# Power_Input.net
KiCad netlist of a schematic drawn in Altium Designer
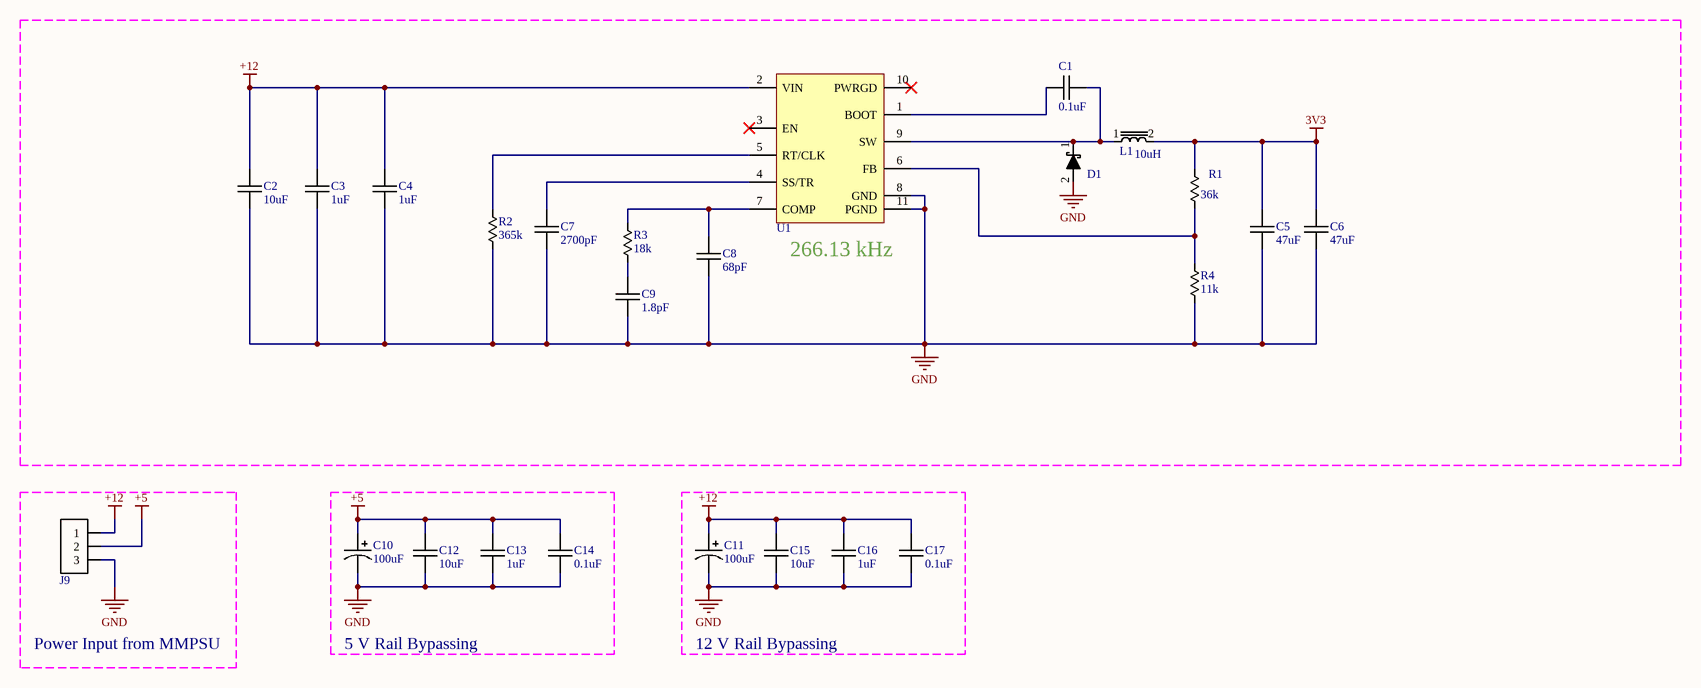
[diagram p0: Power_Input.SchDoc]

(export (version "E")
  (design (tool "Eeschema 10.0.6"))
  (components
    (comp (ref "C1")
      (value "0.1uF")
      (footprint "chip_0603")
      (description "CAP, 0.1uF, ±10%, 16V, X7R, 0603")
      (fields (field (name "PART NUMBER") "CAP-00542") (field (name "TOLERANCE") "±10%"))
      (libsource (lib "Capacitors$") (part "CAP-00542"))
    )
    (comp (ref "C2")
      (value "10uF")
      (footprint "chip_1206")
      (description "CAP, 10uF, ±10%, 25V, X7R, 1206")
      (fields (field (name "PART NUMBER") "CAP-00539") (field (name "TOLERANCE") "±10%"))
      (libsource (lib "Capacitors$") (part "CAP-00539"))
    )
    (comp (ref "C3")
      (value "1uF")
      (footprint "chip_0805")
      (description "CAP, 1uF, 10%, 25V, X7R, 0805")
      (fields (field (name "PART NUMBER") "CAP-00108") (field (name "TOLERANCE") "10%"))
      (libsource (lib "Capacitors$") (part "CAP-00108"))
    )
    (comp (ref "C4")
      (value "1uF")
      (footprint "chip_0805")
      (description "CAP, 1uF, 10%, 25V, X7R, 0805")
      (fields (field (name "PART NUMBER") "CAP-00108") (field (name "TOLERANCE") "10%"))
      (libsource (lib "Capacitors$") (part "CAP-00108"))
    )
    (comp (ref "C5")
      (value "47uF")
      (footprint "chip_1210")
      (description "CAP, 47uF, ±20%, 10V, X7R, 1210")
      (fields (field (name "PART NUMBER") "CAP-00593") (field (name "TOLERANCE") "±20%"))
      (libsource (lib "Capacitors$") (part "CAP-00593"))
    )
    (comp (ref "C6")
      (value "47uF")
      (footprint "chip_1210")
      (description "CAP, 47uF, ±20%, 10V, X7R, 1210")
      (fields (field (name "PART NUMBER") "CAP-00593") (field (name "TOLERANCE") "±20%"))
      (libsource (lib "Capacitors$") (part "CAP-00593"))
    )
    (comp (ref "C7")
      (value "2700pF")
      (footprint "chip_0603")
      (description "CAP, 2700pF, ±2%, 50V, C0G, 0603")
      (fields (field (name "PART NUMBER") "CAP-00434") (field (name "TOLERANCE") "±2%"))
      (libsource (lib "Capacitors$") (part "CAP-00434"))
    )
    (comp (ref "C8")
      (value "68pF")
      (footprint "chip_0603")
      (description "CAP, 68pF, ±2%, 50V, C0G, 0603")
      (fields (field (name "PART NUMBER") "CAP-00462") (field (name "TOLERANCE") "±2%"))
      (libsource (lib "Capacitors$") (part "CAP-00462"))
    )
    (comp (ref "C9")
      (value "1.8pF")
      (footprint "chip_0603")
      (description "CAP, 1.8pF, ±0.1pF, 50V, C0G, 0603")
      (fields (field (name "PART NUMBER") "CAP-00384") (field (name "TOLERANCE") "±0.1pF"))
      (libsource (lib "Capacitors$") (part "CAP-00384"))
    )
    (comp (ref "C10")
      (value "100uF")
      (footprint "can_2_0")
      (description "CAP, 100uF, 20%, 10V, Al, Radial/Can")
      (fields (field (name "PART NUMBER") "CAP-00238") (field (name "TOLERANCE") "20%"))
      (libsource (lib "Capacitors$") (part "CAP-00238"))
    )
    (comp (ref "C11")
      (value "100uF")
      (footprint "can_2_0")
      (description "CAP, 100uF, 20%, 10V, Al, Radial/Can")
      (fields (field (name "PART NUMBER") "CAP-00238") (field (name "TOLERANCE") "20%"))
      (libsource (lib "Capacitors$") (part "CAP-00238"))
    )
    (comp (ref "C12")
      (value "10uF")
      (footprint "chip_0805")
      (description "CAP, 10uF, 10%, 10V, X7R, 0805")
      (fields (field (name "PART NUMBER") "CAP-00131") (field (name "TOLERANCE") "10%"))
      (libsource (lib "Capacitors$") (part "CAP-00131"))
    )
    (comp (ref "C13")
      (value "1uF")
      (footprint "chip_0805")
      (description "CAP, 1uF, 10%, 10V, X7R, 0805")
      (fields (field (name "PART NUMBER") "CAP-00111") (field (name "TOLERANCE") "10%"))
      (libsource (lib "Capacitors$") (part "CAP-00111"))
    )
    (comp (ref "C14")
      (value "0.1uF")
      (footprint "chip_0603")
      (description "CAP, 0.1uF, ±10%, 16V, X7R, 0603")
      (fields (field (name "PART NUMBER") "CAP-00542") (field (name "TOLERANCE") "±10%"))
      (libsource (lib "Capacitors$") (part "CAP-00542"))
    )
    (comp (ref "C15")
      (value "10uF")
      (footprint "chip_0805")
      (description "CAP, 10uF, 10%, 10V, X7R, 0805")
      (fields (field (name "PART NUMBER") "CAP-00131") (field (name "TOLERANCE") "10%"))
      (libsource (lib "Capacitors$") (part "CAP-00131"))
    )
    (comp (ref "C16")
      (value "1uF")
      (footprint "chip_0805")
      (description "CAP, 1uF, 10%, 10V, X7R, 0805")
      (fields (field (name "PART NUMBER") "CAP-00111") (field (name "TOLERANCE") "10%"))
      (libsource (lib "Capacitors$") (part "CAP-00111"))
    )
    (comp (ref "C17")
      (value "0.1uF")
      (footprint "chip_0603")
      (description "CAP, 0.1uF, ±10%, 16V, X7R, 0603")
      (fields (field (name "PART NUMBER") "CAP-00542") (field (name "TOLERANCE") "±10%"))
      (libsource (lib "Capacitors$") (part "CAP-00542"))
    )
    (comp (ref "D1")
      (value "diode_2")
      (footprint "sod123_0")
      (description "Dio Shtky, 2A, 0.43V, 30V, SOD-123")
      (fields (field (name "PART NUMBER") "DIO-00002") (field (name "MANUFACTURER") "ON Semi"))
      (libsource (lib "Diodes$") (part "DIO-00002"))
    )
    (comp (ref "J9")
      (value "conn-3x1_0")
      (footprint "PHOENIX_1991105")
      (description "Terminal Blk, 3 Pos, 20A, 5.0mm Pitch, Screwless, 12-24AWG")
      (fields (field (name "PART NUMBER") "CONN-00097") (field (name "MANUFACTURER") "Phoenix Contact"))
      (libsource (lib "Connectors$") (part "CONN-00097"))
    )
    (comp (ref "L1")
      (value "10uH")
      (footprint "chip_0805")
      (description "Ind, 10uH, 20%, 350mA, 0805")
      (fields (field (name "PART NUMBER") "MAG-00059") (field (name "TOLERANCE") "20%"))
      (libsource (lib "Magnetics$") (part "MAG-00059"))
    )
    (comp (ref "R1")
      (value "36k")
      (footprint "chip_0603")
      (description "RES SMD 36K OHM 1% 1/4W 0603")
      (fields (field (name "PART NUMBER") "RES-00449") (field (name "TOLERANCE") "1%"))
      (libsource (lib "Resistors$") (part "RES-00449"))
    )
    (comp (ref "R2")
      (value "365k")
      (footprint "chip_0603")
      (description "RES SMD 365K OHM 1% 1/10W 0603")
      (fields (field (name "PART NUMBER") "RES-01182") (field (name "TOLERANCE") "±1%"))
      (libsource (lib "Resistors$") (part "RES-01182"))
    )
    (comp (ref "R3")
      (value "18k")
      (footprint "chip_0603")
      (description "RES SMD 18K OHM 1% 1/10W 0603")
      (fields (field (name "PART NUMBER") "RES-00760") (field (name "TOLERANCE") "±1%"))
      (libsource (lib "Resistors$") (part "RES-00760"))
    )
    (comp (ref "R4")
      (value "11k")
      (footprint "chip_0603")
      (description "RES SMD 11K OHM 1% 1/4W 0603")
      (fields (field (name "PART NUMBER") "RES-00314") (field (name "TOLERANCE") "1%"))
      (libsource (lib "Resistors$") (part "RES-00314"))
    )
    (comp (ref "U1")
      (value "TPS54361")
      (footprint "WSON-10_0")
      (description "REG, SW Buck Adj, 3A, 4.5-60V, 2.5MHz, TPS54361")
      (fields (field (name "PART NUMBER") "PWREG-00078") (field (name "MANUFACTURER") "TI"))
      (libsource (lib "Power Reg$") (part "PWREG-00078"))
    )
  )
  (nets
    (net (code "1") (name "+5") (class "Default")
      (node (ref "C10") (pin "1") (pinfunction "1_1") (pintype "passive"))
      (node (ref "C12") (pin "1") (pinfunction "1_1") (pintype "passive"))
      (node (ref "C13") (pin "1") (pinfunction "1_1") (pintype "passive"))
      (node (ref "C14") (pin "1") (pinfunction "1_1") (pintype "passive"))
      (node (ref "J9") (pin "2") (pinfunction "2_2") (pintype "passive"))
    )
    (net (code "2") (name "+12") (class "Default")
      (node (ref "C11") (pin "1") (pinfunction "1_1") (pintype "passive"))
      (node (ref "C15") (pin "1") (pinfunction "1_1") (pintype "passive"))
      (node (ref "C16") (pin "1") (pinfunction "1_1") (pintype "passive"))
      (node (ref "C17") (pin "1") (pinfunction "1_1") (pintype "passive"))
      (node (ref "C2") (pin "1") (pinfunction "1_1") (pintype "passive"))
      (node (ref "C3") (pin "1") (pinfunction "1_1") (pintype "passive"))
      (node (ref "C4") (pin "1") (pinfunction "1_1") (pintype "passive"))
      (node (ref "J9") (pin "1") (pinfunction "1_1") (pintype "passive"))
      (node (ref "U1") (pin "2") (pinfunction "VIN_2") (pintype "passive"))
    )
    (net (code "3") (name "3V3") (class "Default")
      (node (ref "C5") (pin "1") (pinfunction "1_1") (pintype "passive"))
      (node (ref "C6") (pin "1") (pinfunction "1_1") (pintype "passive"))
      (node (ref "L1") (pin "2") (pinfunction "2_2") (pintype "passive"))
      (node (ref "R1") (pin "1") (pinfunction "1_1") (pintype "passive"))
    )
    (net (code "4") (name "GND") (class "Default")
      (node (ref "C10") (pin "2") (pinfunction "2_2") (pintype "passive"))
      (node (ref "C11") (pin "2") (pinfunction "2_2") (pintype "passive"))
      (node (ref "C12") (pin "2") (pinfunction "2_2") (pintype "passive"))
      (node (ref "C13") (pin "2") (pinfunction "2_2") (pintype "passive"))
      (node (ref "C14") (pin "2") (pinfunction "2_2") (pintype "passive"))
      (node (ref "C15") (pin "2") (pinfunction "2_2") (pintype "passive"))
      (node (ref "C16") (pin "2") (pinfunction "2_2") (pintype "passive"))
      (node (ref "C17") (pin "2") (pinfunction "2_2") (pintype "passive"))
      (node (ref "C2") (pin "2") (pinfunction "2_2") (pintype "passive"))
      (node (ref "C3") (pin "2") (pinfunction "2_2") (pintype "passive"))
      (node (ref "C4") (pin "2") (pinfunction "2_2") (pintype "passive"))
      (node (ref "C5") (pin "2") (pinfunction "2_2") (pintype "passive"))
      (node (ref "C6") (pin "2") (pinfunction "2_2") (pintype "passive"))
      (node (ref "C7") (pin "2") (pinfunction "2_2") (pintype "passive"))
      (node (ref "C8") (pin "2") (pinfunction "2_2") (pintype "passive"))
      (node (ref "C9") (pin "2") (pinfunction "2_2") (pintype "passive"))
      (node (ref "D1") (pin "2") (pinfunction "2_2") (pintype "passive"))
      (node (ref "J9") (pin "3") (pinfunction "3_3") (pintype "passive"))
      (node (ref "R2") (pin "2") (pinfunction "2_2") (pintype "passive"))
      (node (ref "R4") (pin "2") (pinfunction "2_2") (pintype "passive"))
      (node (ref "U1") (pin "11") (pinfunction "PGND_11") (pintype "passive"))
      (node (ref "U1") (pin "8") (pinfunction "GND_8") (pintype "passive"))
    )
    (net (code "5") (name "Net-(C9-Pad1)") (class "Default")
      (node (ref "C9") (pin "1") (pinfunction "1_1") (pintype "passive"))
      (node (ref "R3") (pin "2") (pinfunction "2_2") (pintype "passive"))
    )
    (net (code "6") (name "Net-(U1-BOOT)") (class "Default")
      (node (ref "C1") (pin "1") (pinfunction "1_1") (pintype "passive"))
      (node (ref "U1") (pin "1") (pinfunction "BOOT_1") (pintype "passive"))
    )
    (net (code "7") (name "Net-(U1-COMP)") (class "Default")
      (node (ref "C8") (pin "1") (pinfunction "1_1") (pintype "passive"))
      (node (ref "R3") (pin "1") (pinfunction "1_1") (pintype "passive"))
      (node (ref "U1") (pin "7") (pinfunction "COMP_7") (pintype "passive"))
    )
    (net (code "8") (name "Net-(U1-FB)") (class "Default")
      (node (ref "R1") (pin "2") (pinfunction "2_2") (pintype "passive"))
      (node (ref "R4") (pin "1") (pinfunction "1_1") (pintype "passive"))
      (node (ref "U1") (pin "6") (pinfunction "FB_6") (pintype "passive"))
    )
    (net (code "9") (name "Net-(U1-RT{slash}CLK)") (class "Default")
      (node (ref "R2") (pin "1") (pinfunction "1_1") (pintype "passive"))
      (node (ref "U1") (pin "5") (pinfunction "RT/CLK_5") (pintype "passive"))
    )
    (net (code "10") (name "Net-(U1-SS{slash}TR)") (class "Default")
      (node (ref "C7") (pin "1") (pinfunction "1_1") (pintype "passive"))
      (node (ref "U1") (pin "4") (pinfunction "SS/TR_4") (pintype "passive"))
    )
    (net (code "11") (name "Net-(U1-SW)") (class "Default")
      (node (ref "C1") (pin "2") (pinfunction "2_2") (pintype "passive"))
      (node (ref "D1") (pin "1") (pinfunction "1_1") (pintype "passive"))
      (node (ref "L1") (pin "1") (pinfunction "1_1") (pintype "passive"))
      (node (ref "U1") (pin "9") (pinfunction "SW_9") (pintype "passive"))
    )
    (net (code "12") (name "unconnected-(U1-EN-Pad3)") (class "Default")
      (node (ref "U1") (pin "3") (pinfunction "EN_3") (pintype "passive+no_connect"))
    )
    (net (code "13") (name "unconnected-(U1-PWRGD-Pad10)") (class "Default")
      (node (ref "U1") (pin "10") (pinfunction "PWRGD_10") (pintype "passive+no_connect"))
    )
  )
)
